# tc9163af-relays.net
KiCad netlist of a schematic drawn in EAGLE
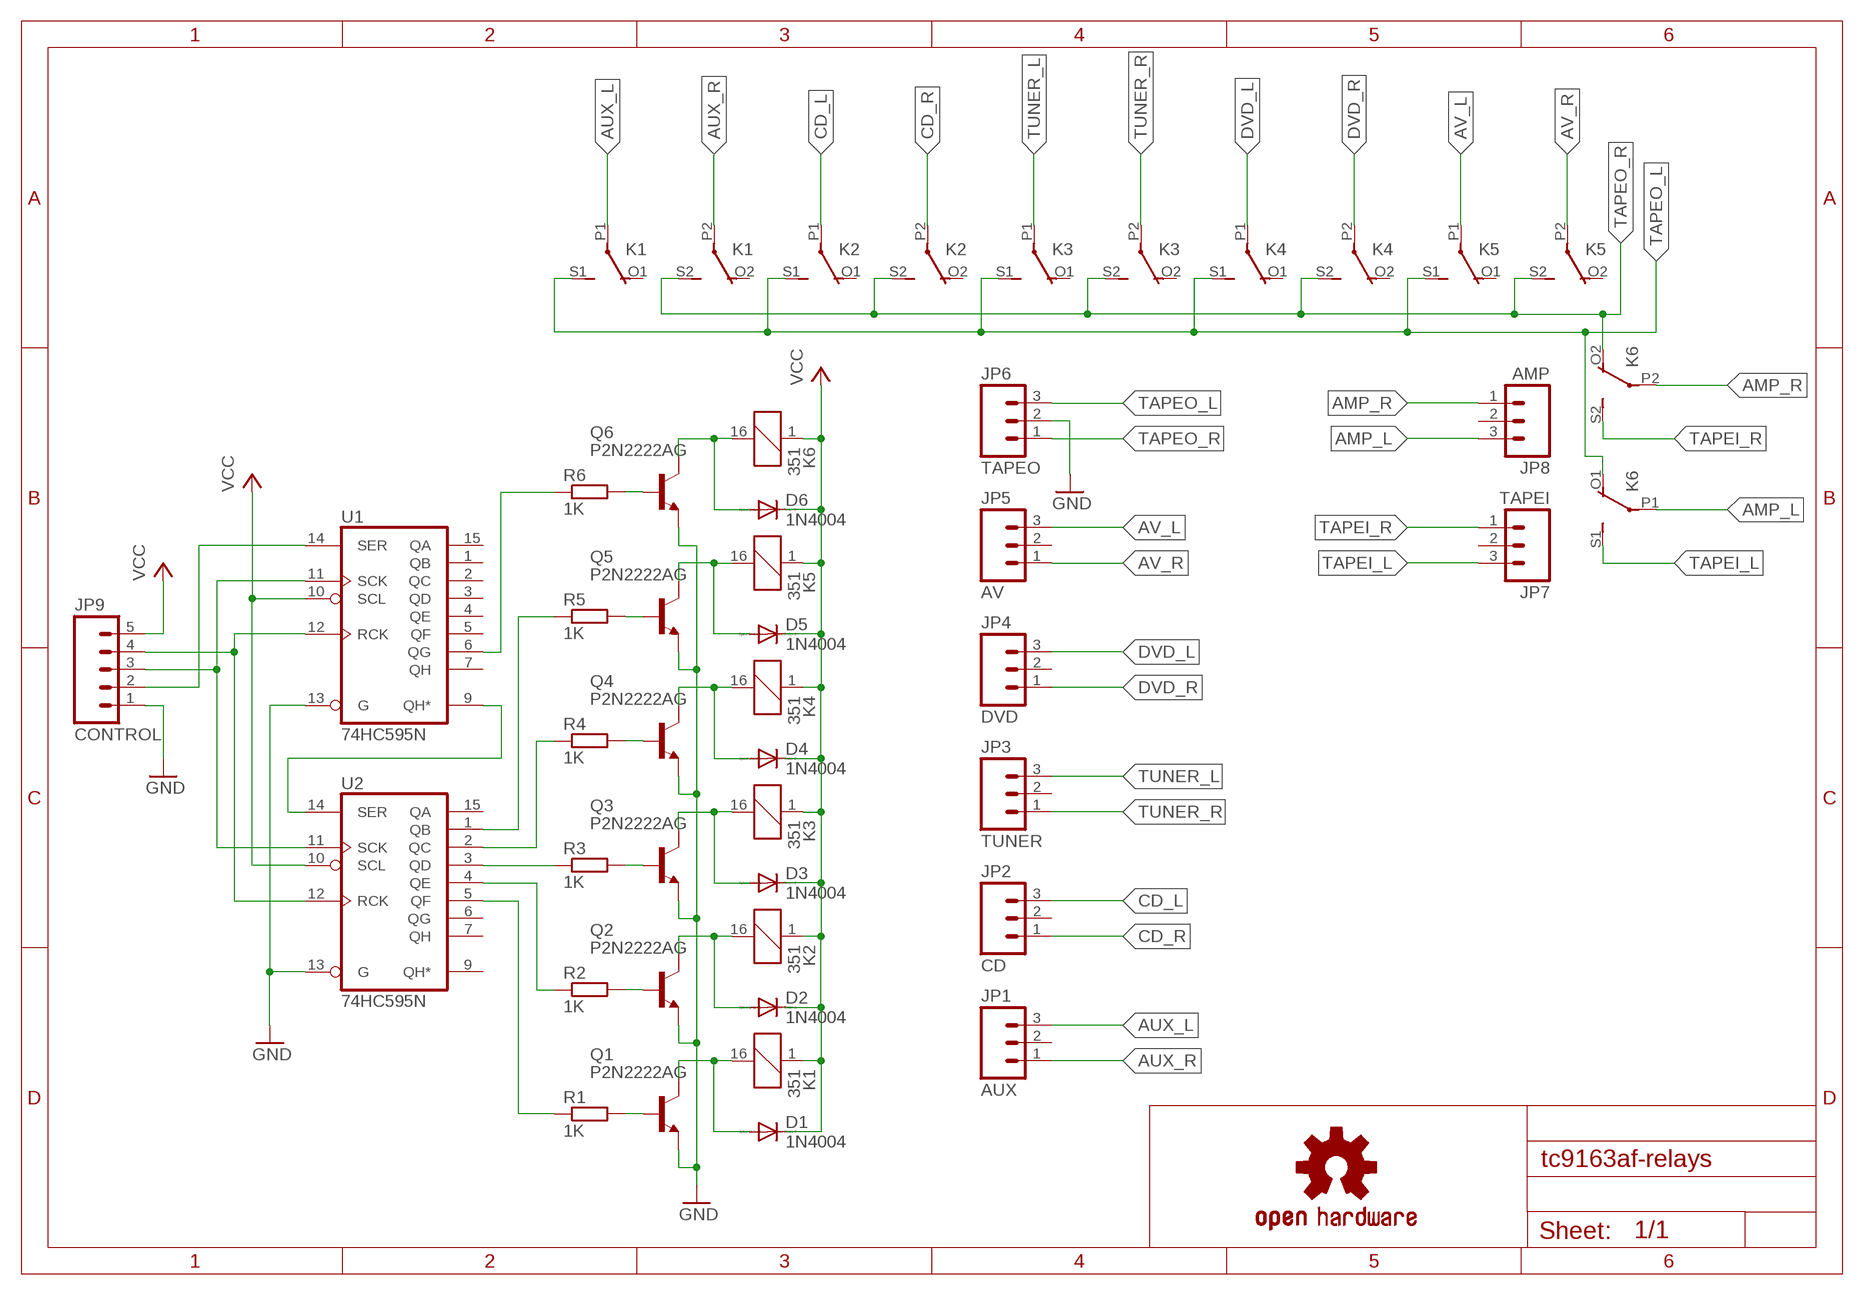
[diagram p0: schematic, sheet 1]

(export (version "E")
  (design (tool "Eeschema 10.0.6"))
  (components
    (comp (ref "D1")
      (value "1N4004")
      (footprint "eagle-import:DO41-10")
      (libsource (lib "eagle-import") (part "1N4004"))
    )
    (comp (ref "D2")
      (value "1N4004")
      (footprint "eagle-import:DO41-10")
      (libsource (lib "eagle-import") (part "1N4004"))
    )
    (comp (ref "D3")
      (value "1N4004")
      (footprint "eagle-import:DO41-10")
      (libsource (lib "eagle-import") (part "1N4004"))
    )
    (comp (ref "D4")
      (value "1N4004")
      (footprint "eagle-import:DO41-10")
      (libsource (lib "eagle-import") (part "1N4004"))
    )
    (comp (ref "D5")
      (value "1N4004")
      (footprint "eagle-import:DO41-10")
      (libsource (lib "eagle-import") (part "1N4004"))
    )
    (comp (ref "D6")
      (value "1N4004")
      (footprint "eagle-import:DO41-10")
      (libsource (lib "eagle-import") (part "1N4004"))
    )
    (comp (ref "JP1")
      (value "AUX")
      (footprint "eagle-import:1X03")
      (libsource (lib "eagle-import") (part "M03PTH"))
    )
    (comp (ref "JP2")
      (value "CD")
      (footprint "eagle-import:1X03")
      (libsource (lib "eagle-import") (part "M03PTH"))
    )
    (comp (ref "JP3")
      (value "TUNER")
      (footprint "eagle-import:1X03")
      (libsource (lib "eagle-import") (part "M03PTH"))
    )
    (comp (ref "JP4")
      (value "DVD")
      (footprint "eagle-import:1X03")
      (libsource (lib "eagle-import") (part "M03PTH"))
    )
    (comp (ref "JP5")
      (value "AV")
      (footprint "eagle-import:1X03")
      (libsource (lib "eagle-import") (part "M03PTH"))
    )
    (comp (ref "JP6")
      (value "TAPEO")
      (footprint "eagle-import:1X03")
      (libsource (lib "eagle-import") (part "M03PTH"))
    )
    (comp (ref "JP7")
      (value "TAPEI")
      (footprint "eagle-import:1X03")
      (libsource (lib "eagle-import") (part "M03PTH"))
    )
    (comp (ref "JP8")
      (value "AMP")
      (footprint "eagle-import:1X03")
      (libsource (lib "eagle-import") (part "M03PTH"))
    )
    (comp (ref "JP9")
      (value "CONTROL")
      (footprint "eagle-import:1X05")
      (libsource (lib "eagle-import") (part "M05PTH"))
    )
    (comp (ref "K1")
      (value "351")
      (footprint "eagle-import:351")
      (libsource (lib "eagle-import") (part "351"))
    )
    (comp (ref "K2")
      (value "351")
      (footprint "eagle-import:351")
      (libsource (lib "eagle-import") (part "351"))
    )
    (comp (ref "K3")
      (value "351")
      (footprint "eagle-import:351")
      (libsource (lib "eagle-import") (part "351"))
    )
    (comp (ref "K4")
      (value "351")
      (footprint "eagle-import:351")
      (libsource (lib "eagle-import") (part "351"))
    )
    (comp (ref "K5")
      (value "351")
      (footprint "eagle-import:351")
      (libsource (lib "eagle-import") (part "351"))
    )
    (comp (ref "K6")
      (value "351")
      (footprint "eagle-import:351")
      (libsource (lib "eagle-import") (part "351"))
    )
    (comp (ref "LOGO1")
      (value "OSHW-LOGOL")
      (footprint "eagle-import:OSHW-LOGO-L")
      (libsource (lib "eagle-import") (part "OSHW-LOGOL"))
    )
    (comp (ref "Q1")
      (value "P2N2222AG")
      (footprint "eagle-import:TO92-EBC")
      (libsource (lib "eagle-import") (part "-NPN-TO92-EBC2N2222"))
    )
    (comp (ref "Q2")
      (value "P2N2222AG")
      (footprint "eagle-import:TO92-EBC")
      (libsource (lib "eagle-import") (part "-NPN-TO92-EBC2N2222"))
    )
    (comp (ref "Q3")
      (value "P2N2222AG")
      (footprint "eagle-import:TO92-EBC")
      (libsource (lib "eagle-import") (part "-NPN-TO92-EBC2N2222"))
    )
    (comp (ref "Q4")
      (value "P2N2222AG")
      (footprint "eagle-import:TO92-EBC")
      (libsource (lib "eagle-import") (part "-NPN-TO92-EBC2N2222"))
    )
    (comp (ref "Q5")
      (value "P2N2222AG")
      (footprint "eagle-import:TO92-EBC")
      (libsource (lib "eagle-import") (part "-NPN-TO92-EBC2N2222"))
    )
    (comp (ref "Q6")
      (value "P2N2222AG")
      (footprint "eagle-import:TO92-EBC")
      (libsource (lib "eagle-import") (part "-NPN-TO92-EBC2N2222"))
    )
    (comp (ref "R1")
      (value "1K")
      (footprint "eagle-import:0207_10")
      (libsource (lib "eagle-import") (part "R-EU_0207/10"))
    )
    (comp (ref "R2")
      (value "1K")
      (footprint "eagle-import:0207_10")
      (libsource (lib "eagle-import") (part "R-EU_0207/10"))
    )
    (comp (ref "R3")
      (value "1K")
      (footprint "eagle-import:0207_10")
      (libsource (lib "eagle-import") (part "R-EU_0207/10"))
    )
    (comp (ref "R4")
      (value "1K")
      (footprint "eagle-import:0207_10")
      (libsource (lib "eagle-import") (part "R-EU_0207/10"))
    )
    (comp (ref "R5")
      (value "1K")
      (footprint "eagle-import:0207_10")
      (libsource (lib "eagle-import") (part "R-EU_0207/10"))
    )
    (comp (ref "R6")
      (value "1K")
      (footprint "eagle-import:0207_10")
      (libsource (lib "eagle-import") (part "R-EU_0207/10"))
    )
    (comp (ref "U1")
      (value "74HC595N")
      (footprint "eagle-import:DIL16")
      (libsource (lib "eagle-import") (part "74595NHC"))
    )
    (comp (ref "U2")
      (value "74HC595N")
      (footprint "eagle-import:DIL16")
      (libsource (lib "eagle-import") (part "74595NHC"))
    )
  )
  (nets
    (net (code "1") (name "AMP_L") (class "Default")
      (node (ref "JP8") (pin "3") (pinfunction "3_3") (pintype "passive"))
      (node (ref "K6") (pin "P1") (pinfunction "P_P1") (pintype "passive"))
    )
    (net (code "2") (name "AMP_R") (class "Default")
      (node (ref "JP8") (pin "1") (pinfunction "1_1") (pintype "passive"))
      (node (ref "K6") (pin "P2") (pinfunction "P_P2") (pintype "passive"))
    )
    (net (code "3") (name "AUX_L") (class "Default")
      (node (ref "JP1") (pin "3") (pinfunction "3_3") (pintype "passive"))
      (node (ref "K1") (pin "P1") (pinfunction "P_P1") (pintype "passive"))
    )
    (net (code "4") (name "AUX_R") (class "Default")
      (node (ref "JP1") (pin "1") (pinfunction "1_1") (pintype "passive"))
      (node (ref "K1") (pin "P2") (pinfunction "P_P2") (pintype "passive"))
    )
    (net (code "5") (name "AV_L") (class "Default")
      (node (ref "JP5") (pin "3") (pinfunction "3_3") (pintype "passive"))
      (node (ref "K5") (pin "P1") (pinfunction "P_P1") (pintype "passive"))
    )
    (net (code "6") (name "AV_R") (class "Default")
      (node (ref "JP5") (pin "1") (pinfunction "1_1") (pintype "passive"))
      (node (ref "K5") (pin "P2") (pinfunction "P_P2") (pintype "passive"))
    )
    (net (code "7") (name "CD_L") (class "Default")
      (node (ref "JP2") (pin "3") (pinfunction "3_3") (pintype "passive"))
      (node (ref "K2") (pin "P1") (pinfunction "P_P1") (pintype "passive"))
    )
    (net (code "8") (name "CD_R") (class "Default")
      (node (ref "JP2") (pin "1") (pinfunction "1_1") (pintype "passive"))
      (node (ref "K2") (pin "P2") (pinfunction "P_P2") (pintype "passive"))
    )
    (net (code "9") (name "DVD_L") (class "Default")
      (node (ref "JP4") (pin "3") (pinfunction "3_3") (pintype "passive"))
      (node (ref "K4") (pin "P1") (pinfunction "P_P1") (pintype "passive"))
    )
    (net (code "10") (name "DVD_R") (class "Default")
      (node (ref "JP4") (pin "1") (pinfunction "1_1") (pintype "passive"))
      (node (ref "K4") (pin "P2") (pinfunction "P_P2") (pintype "passive"))
    )
    (net (code "11") (name "GND") (class "Default")
      (node (ref "JP6") (pin "2") (pinfunction "2_2") (pintype "passive"))
      (node (ref "JP9") (pin "1") (pinfunction "1_1") (pintype "passive"))
      (node (ref "Q1") (pin "E") (pinfunction "E_E") (pintype "passive"))
      (node (ref "Q2") (pin "E") (pinfunction "E_E") (pintype "passive"))
      (node (ref "Q3") (pin "E") (pinfunction "E_E") (pintype "passive"))
      (node (ref "Q4") (pin "E") (pinfunction "E_E") (pintype "passive"))
      (node (ref "Q5") (pin "E") (pinfunction "E_E") (pintype "passive"))
      (node (ref "Q6") (pin "E") (pinfunction "E_E") (pintype "passive"))
      (node (ref "U1") (pin "13") (pinfunction "G_13") (pintype "input"))
      (node (ref "U2") (pin "13") (pinfunction "G_13") (pintype "input"))
    )
    (net (code "12") (name "Net-(K1A-2)") (class "Default")
      (node (ref "D1") (pin "A") (pinfunction "A_A") (pintype "passive"))
      (node (ref "K1") (pin "16") (pinfunction "2_16") (pintype "passive"))
      (node (ref "Q1") (pin "C") (pinfunction "C_C") (pintype "passive"))
    )
    (net (code "13") (name "Net-(K2A-2)") (class "Default")
      (node (ref "D2") (pin "A") (pinfunction "A_A") (pintype "passive"))
      (node (ref "K2") (pin "16") (pinfunction "2_16") (pintype "passive"))
      (node (ref "Q2") (pin "C") (pinfunction "C_C") (pintype "passive"))
    )
    (net (code "14") (name "Net-(K3A-2)") (class "Default")
      (node (ref "D3") (pin "A") (pinfunction "A_A") (pintype "passive"))
      (node (ref "K3") (pin "16") (pinfunction "2_16") (pintype "passive"))
      (node (ref "Q3") (pin "C") (pinfunction "C_C") (pintype "passive"))
    )
    (net (code "15") (name "Net-(K4A-2)") (class "Default")
      (node (ref "D4") (pin "A") (pinfunction "A_A") (pintype "passive"))
      (node (ref "K4") (pin "16") (pinfunction "2_16") (pintype "passive"))
      (node (ref "Q4") (pin "C") (pinfunction "C_C") (pintype "passive"))
    )
    (net (code "16") (name "Net-(K5A-2)") (class "Default")
      (node (ref "D5") (pin "A") (pinfunction "A_A") (pintype "passive"))
      (node (ref "K5") (pin "16") (pinfunction "2_16") (pintype "passive"))
      (node (ref "Q5") (pin "C") (pinfunction "C_C") (pintype "passive"))
    )
    (net (code "17") (name "Net-(K6A-2)") (class "Default")
      (node (ref "D6") (pin "A") (pinfunction "A_A") (pintype "passive"))
      (node (ref "K6") (pin "16") (pinfunction "2_16") (pintype "passive"))
      (node (ref "Q6") (pin "C") (pinfunction "C_C") (pintype "passive"))
    )
    (net (code "18") (name "Net-(Q1-PadB)") (class "Default")
      (node (ref "Q1") (pin "B") (pinfunction "B_B") (pintype "passive"))
      (node (ref "R1") (pin "2") (pinfunction "2_2") (pintype "passive"))
    )
    (net (code "19") (name "Net-(Q2-PadB)") (class "Default")
      (node (ref "Q2") (pin "B") (pinfunction "B_B") (pintype "passive"))
      (node (ref "R2") (pin "2") (pinfunction "2_2") (pintype "passive"))
    )
    (net (code "20") (name "Net-(Q3-PadB)") (class "Default")
      (node (ref "Q3") (pin "B") (pinfunction "B_B") (pintype "passive"))
      (node (ref "R3") (pin "2") (pinfunction "2_2") (pintype "passive"))
    )
    (net (code "21") (name "Net-(Q4-PadB)") (class "Default")
      (node (ref "Q4") (pin "B") (pinfunction "B_B") (pintype "passive"))
      (node (ref "R4") (pin "2") (pinfunction "2_2") (pintype "passive"))
    )
    (net (code "22") (name "Net-(Q5-PadB)") (class "Default")
      (node (ref "Q5") (pin "B") (pinfunction "B_B") (pintype "passive"))
      (node (ref "R5") (pin "2") (pinfunction "2_2") (pintype "passive"))
    )
    (net (code "23") (name "Net-(Q6-PadB)") (class "Default")
      (node (ref "Q6") (pin "B") (pinfunction "B_B") (pintype "passive"))
      (node (ref "R6") (pin "2") (pinfunction "2_2") (pintype "passive"))
    )
    (net (code "24") (name "Net-(U1A-QG)") (class "Default")
      (node (ref "R6") (pin "1") (pinfunction "1_1") (pintype "passive"))
      (node (ref "U1") (pin "6") (pinfunction "QG_6") (pintype "tri_state"))
    )
    (net (code "25") (name "Net-(U1A-QH*)") (class "Default")
      (node (ref "U1") (pin "9") (pinfunction "QH*_9") (pintype "tri_state"))
      (node (ref "U2") (pin "14") (pinfunction "SER_14") (pintype "input"))
    )
    (net (code "26") (name "Net-(U1A-RCK)") (class "Default")
      (node (ref "JP9") (pin "4") (pinfunction "4_4") (pintype "passive"))
      (node (ref "U1") (pin "12") (pinfunction "RCK_12") (pintype "input"))
      (node (ref "U2") (pin "12") (pinfunction "RCK_12") (pintype "input"))
    )
    (net (code "27") (name "Net-(U1A-SCK)") (class "Default")
      (node (ref "JP9") (pin "3") (pinfunction "3_3") (pintype "passive"))
      (node (ref "U1") (pin "11") (pinfunction "SCK_11") (pintype "input"))
      (node (ref "U2") (pin "11") (pinfunction "SCK_11") (pintype "input"))
    )
    (net (code "28") (name "Net-(U1A-SER)") (class "Default")
      (node (ref "JP9") (pin "2") (pinfunction "2_2") (pintype "passive"))
      (node (ref "U1") (pin "14") (pinfunction "SER_14") (pintype "input"))
    )
    (net (code "29") (name "Net-(U2A-QB)") (class "Default")
      (node (ref "R5") (pin "1") (pinfunction "1_1") (pintype "passive"))
      (node (ref "U2") (pin "1") (pinfunction "QB_1") (pintype "tri_state"))
    )
    (net (code "30") (name "Net-(U2A-QC)") (class "Default")
      (node (ref "R4") (pin "1") (pinfunction "1_1") (pintype "passive"))
      (node (ref "U2") (pin "2") (pinfunction "QC_2") (pintype "tri_state"))
    )
    (net (code "31") (name "Net-(U2A-QD)") (class "Default")
      (node (ref "R3") (pin "1") (pinfunction "1_1") (pintype "passive"))
      (node (ref "U2") (pin "3") (pinfunction "QD_3") (pintype "tri_state"))
    )
    (net (code "32") (name "Net-(U2A-QE)") (class "Default")
      (node (ref "R2") (pin "1") (pinfunction "1_1") (pintype "passive"))
      (node (ref "U2") (pin "4") (pinfunction "QE_4") (pintype "tri_state"))
    )
    (net (code "33") (name "Net-(U2A-QF)") (class "Default")
      (node (ref "R1") (pin "1") (pinfunction "1_1") (pintype "passive"))
      (node (ref "U2") (pin "5") (pinfunction "QF_5") (pintype "tri_state"))
    )
    (net (code "34") (name "TAPEI_L") (class "Default")
      (node (ref "JP7") (pin "3") (pinfunction "3_3") (pintype "passive"))
      (node (ref "K6") (pin "S1") (pinfunction "S_S1") (pintype "passive"))
    )
    (net (code "35") (name "TAPEI_R") (class "Default")
      (node (ref "JP7") (pin "1") (pinfunction "1_1") (pintype "passive"))
      (node (ref "K6") (pin "S2") (pinfunction "S_S2") (pintype "passive"))
    )
    (net (code "36") (name "TAPEO_L") (class "Default")
      (node (ref "JP6") (pin "3") (pinfunction "3_3") (pintype "passive"))
      (node (ref "K1") (pin "S1") (pinfunction "S_S1") (pintype "passive"))
      (node (ref "K2") (pin "S1") (pinfunction "S_S1") (pintype "passive"))
      (node (ref "K3") (pin "S1") (pinfunction "S_S1") (pintype "passive"))
      (node (ref "K4") (pin "S1") (pinfunction "S_S1") (pintype "passive"))
      (node (ref "K5") (pin "S1") (pinfunction "S_S1") (pintype "passive"))
      (node (ref "K6") (pin "O1") (pinfunction "O_O1") (pintype "passive"))
    )
    (net (code "37") (name "TAPEO_R") (class "Default")
      (node (ref "JP6") (pin "1") (pinfunction "1_1") (pintype "passive"))
      (node (ref "K1") (pin "S2") (pinfunction "S_S2") (pintype "passive"))
      (node (ref "K2") (pin "S2") (pinfunction "S_S2") (pintype "passive"))
      (node (ref "K3") (pin "S2") (pinfunction "S_S2") (pintype "passive"))
      (node (ref "K4") (pin "S2") (pinfunction "S_S2") (pintype "passive"))
      (node (ref "K5") (pin "S2") (pinfunction "S_S2") (pintype "passive"))
      (node (ref "K6") (pin "O2") (pinfunction "O_O2") (pintype "passive"))
    )
    (net (code "38") (name "TUNER_L") (class "Default")
      (node (ref "JP3") (pin "3") (pinfunction "3_3") (pintype "passive"))
      (node (ref "K3") (pin "P1") (pinfunction "P_P1") (pintype "passive"))
    )
    (net (code "39") (name "TUNER_R") (class "Default")
      (node (ref "JP3") (pin "1") (pinfunction "1_1") (pintype "passive"))
      (node (ref "K3") (pin "P2") (pinfunction "P_P2") (pintype "passive"))
    )
    (net (code "40") (name "VCC") (class "Default")
      (node (ref "D1") (pin "C") (pinfunction "C_C") (pintype "passive"))
      (node (ref "D2") (pin "C") (pinfunction "C_C") (pintype "passive"))
      (node (ref "D3") (pin "C") (pinfunction "C_C") (pintype "passive"))
      (node (ref "D4") (pin "C") (pinfunction "C_C") (pintype "passive"))
      (node (ref "D5") (pin "C") (pinfunction "C_C") (pintype "passive"))
      (node (ref "D6") (pin "C") (pinfunction "C_C") (pintype "passive"))
      (node (ref "JP9") (pin "5") (pinfunction "5_5") (pintype "passive"))
      (node (ref "K1") (pin "1") (pinfunction "1_1") (pintype "passive"))
      (node (ref "K2") (pin "1") (pinfunction "1_1") (pintype "passive"))
      (node (ref "K3") (pin "1") (pinfunction "1_1") (pintype "passive"))
      (node (ref "K4") (pin "1") (pinfunction "1_1") (pintype "passive"))
      (node (ref "K5") (pin "1") (pinfunction "1_1") (pintype "passive"))
      (node (ref "K6") (pin "1") (pinfunction "1_1") (pintype "passive"))
      (node (ref "U1") (pin "10") (pinfunction "SCL_10") (pintype "input"))
      (node (ref "U2") (pin "10") (pinfunction "SCL_10") (pintype "input"))
    )
    (net (code "41") (name "unconnected-(JP1-Pad2)") (class "Default")
      (node (ref "JP1") (pin "2") (pinfunction "2_2") (pintype "passive"))
    )
    (net (code "42") (name "unconnected-(JP2-Pad2)") (class "Default")
      (node (ref "JP2") (pin "2") (pinfunction "2_2") (pintype "passive"))
    )
    (net (code "43") (name "unconnected-(JP3-Pad2)") (class "Default")
      (node (ref "JP3") (pin "2") (pinfunction "2_2") (pintype "passive"))
    )
    (net (code "44") (name "unconnected-(JP4-Pad2)") (class "Default")
      (node (ref "JP4") (pin "2") (pinfunction "2_2") (pintype "passive"))
    )
    (net (code "45") (name "unconnected-(JP5-Pad2)") (class "Default")
      (node (ref "JP5") (pin "2") (pinfunction "2_2") (pintype "passive"))
    )
    (net (code "46") (name "unconnected-(JP7-Pad2)") (class "Default")
      (node (ref "JP7") (pin "2") (pinfunction "2_2") (pintype "passive"))
    )
    (net (code "47") (name "unconnected-(JP8-Pad2)") (class "Default")
      (node (ref "JP8") (pin "2") (pinfunction "2_2") (pintype "passive"))
    )
    (net (code "48") (name "unconnected-(K1B-O-PadO1)") (class "Default")
      (node (ref "K1") (pin "O1") (pinfunction "O_O1") (pintype "passive"))
    )
    (net (code "49") (name "unconnected-(K1C-O-PadO2)") (class "Default")
      (node (ref "K1") (pin "O2") (pinfunction "O_O2") (pintype "passive"))
    )
    (net (code "50") (name "unconnected-(K2B-O-PadO1)") (class "Default")
      (node (ref "K2") (pin "O1") (pinfunction "O_O1") (pintype "passive"))
    )
    (net (code "51") (name "unconnected-(K2C-O-PadO2)") (class "Default")
      (node (ref "K2") (pin "O2") (pinfunction "O_O2") (pintype "passive"))
    )
    (net (code "52") (name "unconnected-(K3B-O-PadO1)") (class "Default")
      (node (ref "K3") (pin "O1") (pinfunction "O_O1") (pintype "passive"))
    )
    (net (code "53") (name "unconnected-(K3C-O-PadO2)") (class "Default")
      (node (ref "K3") (pin "O2") (pinfunction "O_O2") (pintype "passive"))
    )
    (net (code "54") (name "unconnected-(K4B-O-PadO1)") (class "Default")
      (node (ref "K4") (pin "O1") (pinfunction "O_O1") (pintype "passive"))
    )
    (net (code "55") (name "unconnected-(K4C-O-PadO2)") (class "Default")
      (node (ref "K4") (pin "O2") (pinfunction "O_O2") (pintype "passive"))
    )
    (net (code "56") (name "unconnected-(K5B-O-PadO1)") (class "Default")
      (node (ref "K5") (pin "O1") (pinfunction "O_O1") (pintype "passive"))
    )
    (net (code "57") (name "unconnected-(K5C-O-PadO2)") (class "Default")
      (node (ref "K5") (pin "O2") (pinfunction "O_O2") (pintype "passive"))
    )
    (net (code "58") (name "unconnected-(U1A-QA-Pad15)") (class "Default")
      (node (ref "U1") (pin "15") (pinfunction "QA_15") (pintype "tri_state"))
    )
    (net (code "59") (name "unconnected-(U1A-QB-Pad1)") (class "Default")
      (node (ref "U1") (pin "1") (pinfunction "QB_1") (pintype "tri_state"))
    )
    (net (code "60") (name "unconnected-(U1A-QC-Pad2)") (class "Default")
      (node (ref "U1") (pin "2") (pinfunction "QC_2") (pintype "tri_state"))
    )
    (net (code "61") (name "unconnected-(U1A-QD-Pad3)") (class "Default")
      (node (ref "U1") (pin "3") (pinfunction "QD_3") (pintype "tri_state"))
    )
    (net (code "62") (name "unconnected-(U1A-QE-Pad4)") (class "Default")
      (node (ref "U1") (pin "4") (pinfunction "QE_4") (pintype "tri_state"))
    )
    (net (code "63") (name "unconnected-(U1A-QF-Pad5)") (class "Default")
      (node (ref "U1") (pin "5") (pinfunction "QF_5") (pintype "tri_state"))
    )
    (net (code "64") (name "unconnected-(U1A-QH-Pad7)") (class "Default")
      (node (ref "U1") (pin "7") (pinfunction "QH_7") (pintype "tri_state"))
    )
    (net (code "65") (name "unconnected-(U2A-QA-Pad15)") (class "Default")
      (node (ref "U2") (pin "15") (pinfunction "QA_15") (pintype "tri_state"))
    )
    (net (code "66") (name "unconnected-(U2A-QG-Pad6)") (class "Default")
      (node (ref "U2") (pin "6") (pinfunction "QG_6") (pintype "tri_state"))
    )
    (net (code "67") (name "unconnected-(U2A-QH*-Pad9)") (class "Default")
      (node (ref "U2") (pin "9") (pinfunction "QH*_9") (pintype "tri_state"))
    )
    (net (code "68") (name "unconnected-(U2A-QH-Pad7)") (class "Default")
      (node (ref "U2") (pin "7") (pinfunction "QH_7") (pintype "tri_state"))
    )
  )
)
